# LorRaBaseBoard.net
KiCad netlist of a schematic drawn in EAGLE
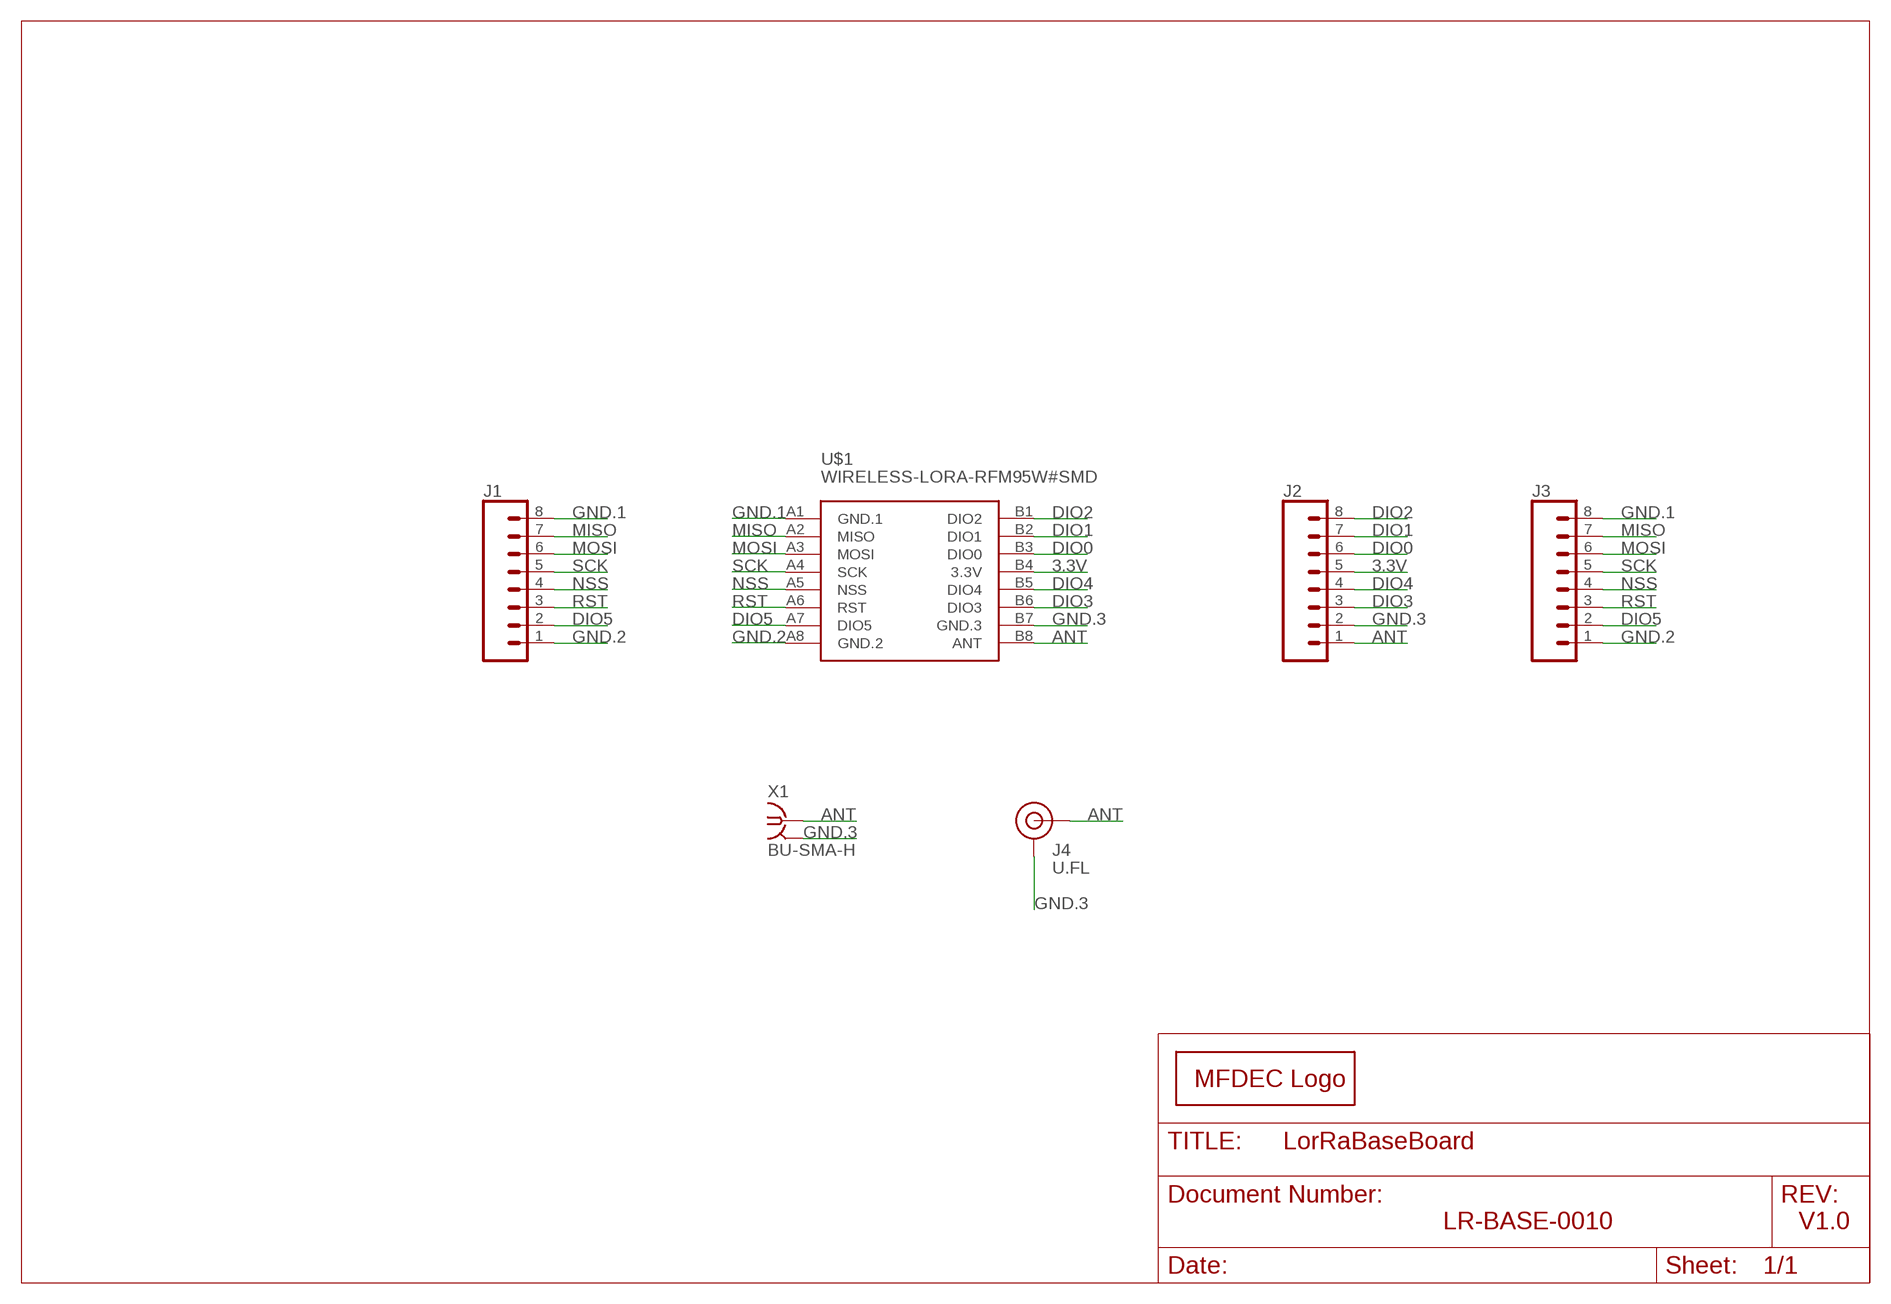
[diagram p0: schematic, sheet 1]

(export (version "E")
  (design (tool "Eeschema 10.0.6"))
  (components
    (comp (ref "J1")
      (value "CONN_08NO_SILK_FEMALE_PTH")
      (footprint "eagle-import:1X08_NO_SILK")
      (libsource (lib "eagle-import") (part "CONN_08NO_SILK_FEMALE_PTH"))
    )
    (comp (ref "J2")
      (value "CONN_08NO_SILK_FEMALE_PTH")
      (footprint "eagle-import:1X08_NO_SILK")
      (libsource (lib "eagle-import") (part "CONN_08NO_SILK_FEMALE_PTH"))
    )
    (comp (ref "J3")
      (value "CONN_08NO_SILK_FEMALE_PTH")
      (footprint "eagle-import:1X08_NO_SILK")
      (libsource (lib "eagle-import") (part "CONN_08NO_SILK_FEMALE_PTH"))
    )
    (comp (ref "J4")
      (value "U.FL")
      (footprint "eagle-import:U.FL")
      (libsource (lib "eagle-import") (part "U.FL2PIN"))
    )
    (comp (ref "LOGO1")
      (value "MFDECLOGO_SQ_8MM")
      (footprint "eagle-import:MFDEC_SQ_8MM")
      (libsource (lib "eagle-import") (part "MFDECLOGO_SQ_8MM"))
    )
    (comp (ref "U$1")
      (value "WIRELESS-LORA-RFM95W#SMD")
      (footprint "eagle-import:WIRELESS-LORA-RFM95W#SMD")
      (libsource (lib "eagle-import") (part "WIRELESS-LORA-RFM95W#SMD"))
    )
    (comp (ref "X1")
      (value "BU-SMA-H")
      (footprint "eagle-import:BU-SMA-H")
      (libsource (lib "eagle-import") (part "BU-SMA-H"))
    )
  )
  (nets
    (net (code "1") (name "/3.3V") (class "Default")
      (node (ref "J2") (pin "5") (pinfunction "5_5") (pintype "passive"))
      (node (ref "U$1") (pin "B4") (pinfunction "3.3V_B4") (pintype "power_in"))
    )
    (net (code "2") (name "/ANT") (class "Default")
      (node (ref "J2") (pin "1") (pinfunction "1_1") (pintype "passive"))
      (node (ref "J4") (pin "FEED") (pinfunction "SIGNAL_FEED") (pintype "bidirectional"))
      (node (ref "U$1") (pin "B8") (pinfunction "ANT_B8") (pintype "passive"))
      (node (ref "X1") (pin "1") (pinfunction "1_1") (pintype "passive"))
    )
    (net (code "3") (name "/DIO0") (class "Default")
      (node (ref "J2") (pin "6") (pinfunction "6_6") (pintype "passive"))
      (node (ref "U$1") (pin "B3") (pinfunction "DIO0_B3") (pintype "bidirectional"))
    )
    (net (code "4") (name "/DIO1") (class "Default")
      (node (ref "J2") (pin "7") (pinfunction "7_7") (pintype "passive"))
      (node (ref "U$1") (pin "B2") (pinfunction "DIO1_B2") (pintype "bidirectional"))
    )
    (net (code "5") (name "/DIO2") (class "Default")
      (node (ref "J2") (pin "8") (pinfunction "8_8") (pintype "passive"))
      (node (ref "U$1") (pin "B1") (pinfunction "DIO2_B1") (pintype "bidirectional"))
    )
    (net (code "6") (name "/DIO3") (class "Default")
      (node (ref "J2") (pin "3") (pinfunction "3_3") (pintype "passive"))
      (node (ref "U$1") (pin "B6") (pinfunction "DIO3_B6") (pintype "bidirectional"))
    )
    (net (code "7") (name "/DIO4") (class "Default")
      (node (ref "J2") (pin "4") (pinfunction "4_4") (pintype "passive"))
      (node (ref "U$1") (pin "B5") (pinfunction "DIO4_B5") (pintype "bidirectional"))
    )
    (net (code "8") (name "/DIO5") (class "Default")
      (node (ref "J1") (pin "2") (pinfunction "2_2") (pintype "passive"))
      (node (ref "J3") (pin "2") (pinfunction "2_2") (pintype "passive"))
      (node (ref "U$1") (pin "A7") (pinfunction "DIO5_A7") (pintype "bidirectional"))
    )
    (net (code "9") (name "/GND.1") (class "Default")
      (node (ref "J1") (pin "8") (pinfunction "8_8") (pintype "passive"))
      (node (ref "J3") (pin "8") (pinfunction "8_8") (pintype "passive"))
      (node (ref "U$1") (pin "A1") (pinfunction "GND.1_A1") (pintype "power_in"))
    )
    (net (code "10") (name "/GND.2") (class "Default")
      (node (ref "J1") (pin "1") (pinfunction "1_1") (pintype "passive"))
      (node (ref "J3") (pin "1") (pinfunction "1_1") (pintype "passive"))
      (node (ref "U$1") (pin "A8") (pinfunction "GND.2_A8") (pintype "power_in"))
    )
    (net (code "11") (name "/GND.3") (class "Default")
      (node (ref "J2") (pin "2") (pinfunction "2_2") (pintype "passive"))
      (node (ref "J4") (pin "1") (pinfunction "GND_1") (pintype "bidirectional"))
      (node (ref "J4") (pin "2") (pinfunction "GND_2") (pintype "bidirectional"))
      (node (ref "U$1") (pin "B7") (pinfunction "GND.3_B7") (pintype "power_in"))
      (node (ref "X1") (pin "2") (pinfunction "2_2") (pintype "passive"))
      (node (ref "X1") (pin "3") (pinfunction "2_3") (pintype "passive"))
      (node (ref "X1") (pin "4") (pinfunction "2_4") (pintype "passive"))
      (node (ref "X1") (pin "5") (pinfunction "2_5") (pintype "passive"))
    )
    (net (code "12") (name "/MISO") (class "Default")
      (node (ref "J1") (pin "7") (pinfunction "7_7") (pintype "passive"))
      (node (ref "J3") (pin "7") (pinfunction "7_7") (pintype "passive"))
      (node (ref "U$1") (pin "A2") (pinfunction "MISO_A2") (pintype "bidirectional"))
    )
    (net (code "13") (name "/MOSI") (class "Default")
      (node (ref "J1") (pin "6") (pinfunction "6_6") (pintype "passive"))
      (node (ref "J3") (pin "6") (pinfunction "6_6") (pintype "passive"))
      (node (ref "U$1") (pin "A3") (pinfunction "MOSI_A3") (pintype "bidirectional"))
    )
    (net (code "14") (name "/NSS") (class "Default")
      (node (ref "J1") (pin "4") (pinfunction "4_4") (pintype "passive"))
      (node (ref "J3") (pin "4") (pinfunction "4_4") (pintype "passive"))
      (node (ref "U$1") (pin "A5") (pinfunction "NSS_A5") (pintype "bidirectional"))
    )
    (net (code "15") (name "/RST") (class "Default")
      (node (ref "J1") (pin "3") (pinfunction "3_3") (pintype "passive"))
      (node (ref "J3") (pin "3") (pinfunction "3_3") (pintype "passive"))
      (node (ref "U$1") (pin "A6") (pinfunction "RST_A6") (pintype "bidirectional"))
    )
    (net (code "16") (name "/SCK") (class "Default")
      (node (ref "J1") (pin "5") (pinfunction "5_5") (pintype "passive"))
      (node (ref "J3") (pin "5") (pinfunction "5_5") (pintype "passive"))
      (node (ref "U$1") (pin "A4") (pinfunction "SCK_A4") (pintype "bidirectional"))
    )
  )
)
